# Rail_Station.net
KiCad netlist of a schematic drawn in Altium Designer
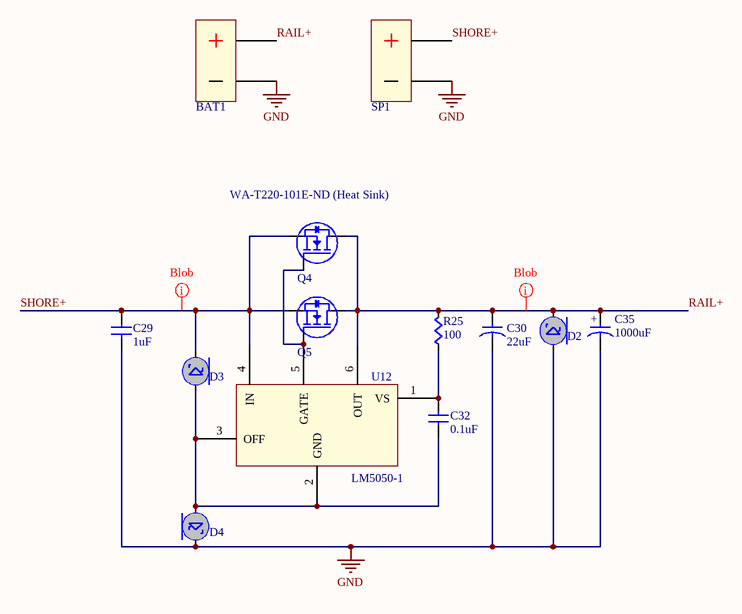
[diagram p0: Rail Station.SchDoc]

(export (version "E")
  (design (tool "Eeschema 10.0.6"))
  (components
    (comp (ref "BAT1")
      (value "BATWIRE")
      (footprint "BATWIRE12")
      (description "Two large gauge leads soldered directly to the board.")
      (libsource (lib "SubjuGator8") (part "BATWIRE"))
    )
    (comp (ref "C29")
      (value "1uF")
      (footprint "CAPC0603")
      (fields (field (name "Comment") "Cap"))
      (libsource (lib "SubjuGator8") (part "Cap"))
    )
    (comp (ref "C30")
      (value "22uF")
      (footprint "CAP22uF100V")
      (fields (field (name "Comment") "CapPol"))
      (libsource (lib "") (part "CapPol_1"))
    )
    (comp (ref "C32")
      (value "0.1uF")
      (footprint "CAPC0603")
      (fields (field (name "Comment") "Cap"))
      (libsource (lib "SubjuGator8") (part "Cap"))
    )
    (comp (ref "C35")
      (value "1000uF")
      (footprint "CAP1000uF")
      (fields (field (name "Comment") "CapPol"))
      (libsource (lib "SubjuGator8") (part "CapPol"))
    )
    (comp (ref "D2")
      (value "SMBJ60A-13-F")
      (footprint "SMBJ60A-13-F")
      (description "TVS UNIDIRECT 600W 60V SMB")
      (libsource (lib "SubjuGator8") (part "SMBJ60A-13-F"))
    )
    (comp (ref "D3")
      (value "SS16T3G")
      (footprint "SS16T3G")
      (description "DIODE SCHOTTKY 60V 1A SMA")
      (libsource (lib "") (part "SS16T3G_1"))
    )
    (comp (ref "D4")
      (value "SS16T3G")
      (footprint "SS16T3G")
      (description "DIODE SCHOTTKY 60V 1A SMA")
      (libsource (lib "SubjuGator8") (part "SS16T3G"))
    )
    (comp (ref "Q4")
      (value "IRFB3306PbF")
      (footprint "TO-220AB Heatsink Vertical")
      (description "HEXFET Power MOSFET")
      (libsource (lib "SubjuGator8") (part "IRFx3306PbF"))
    )
    (comp (ref "Q5")
      (value "IRFB3306PbF")
      (footprint "TO-220AB Heatsink Vertical")
      (description "HEXFET Power MOSFET")
      (libsource (lib "SubjuGator8") (part "IRFx3306PbF"))
    )
    (comp (ref "R25")
      (value "100")
      (footprint "RES0603")
      (fields (field (name "Comment") "Res"))
      (libsource (lib "SubjuGator8") (part "Res"))
    )
    (comp (ref "SP1")
      (value "BATWIRE")
      (footprint "BATWIRE12")
      (description "Two large gauge leads soldered directly to the board.")
      (libsource (lib "SubjuGator8") (part "BATWIRE"))
    )
    (comp (ref "U12")
      (value "LM5050-1")
      (footprint "LM5050")
      (description "High-Side OR-ing FET Controller")
      (libsource (lib "SubjuGator8") (part "LM5050"))
    )
  )
  (nets
    (net (code "1") (name "/RAIL+") (class "Default")
      (node (ref "BAT1") (pin "+") (pinfunction "+_+") (pintype "power_in"))
      (node (ref "C30") (pin "1") (pinfunction "A_1") (pintype "passive"))
      (node (ref "C35") (pin "1") (pinfunction "A_1") (pintype "passive"))
      (node (ref "D2") (pin "C") (pinfunction "C_C") (pintype "passive"))
      (node (ref "Q4") (pin "D") (pinfunction "D_D") (pintype "passive"))
      (node (ref "Q5") (pin "D") (pinfunction "D_D") (pintype "passive"))
      (node (ref "R25") (pin "1") (pinfunction "A_1") (pintype "passive"))
      (node (ref "U12") (pin "6") (pinfunction "OUT_6") (pintype "passive"))
    )
    (net (code "2") (name "/SHORE+") (class "Default")
      (node (ref "C29") (pin "1") (pinfunction "A_1") (pintype "passive"))
      (node (ref "D3") (pin "C") (pinfunction "C_C") (pintype "passive"))
      (node (ref "Q4") (pin "S") (pinfunction "S_S") (pintype "passive"))
      (node (ref "Q5") (pin "S") (pinfunction "S_S") (pintype "passive"))
      (node (ref "SP1") (pin "+") (pinfunction "+_+") (pintype "power_in"))
      (node (ref "U12") (pin "4") (pinfunction "IN_4") (pintype "passive"))
    )
    (net (code "3") (name "GND") (class "Default")
      (node (ref "BAT1") (pin "-") (pinfunction "-_-") (pintype "power_in"))
      (node (ref "C29") (pin "2") (pinfunction "B_2") (pintype "passive"))
      (node (ref "C30") (pin "2") (pinfunction "B_2") (pintype "passive"))
      (node (ref "C35") (pin "2") (pinfunction "B_2") (pintype "passive"))
      (node (ref "D2") (pin "A") (pinfunction "A_A") (pintype "passive"))
      (node (ref "D4") (pin "C") (pinfunction "C_C") (pintype "passive"))
      (node (ref "SP1") (pin "-") (pinfunction "-_-") (pintype "power_in"))
    )
    (net (code "4") (name "Net-(C32-A)") (class "Default")
      (node (ref "C32") (pin "1") (pinfunction "A_1") (pintype "passive"))
      (node (ref "R25") (pin "2") (pinfunction "B_2") (pintype "passive"))
      (node (ref "U12") (pin "1") (pinfunction "VS_1") (pintype "passive"))
    )
    (net (code "5") (name "Net-(C32-B)") (class "Default")
      (node (ref "C32") (pin "2") (pinfunction "B_2") (pintype "passive"))
      (node (ref "D3") (pin "A") (pinfunction "A_A") (pintype "passive"))
      (node (ref "D4") (pin "A") (pinfunction "A_A") (pintype "passive"))
      (node (ref "U12") (pin "2") (pinfunction "GND_2") (pintype "passive"))
      (node (ref "U12") (pin "3") (pinfunction "OFF_3") (pintype "passive"))
    )
    (net (code "6") (name "Net-(U12-GATE)") (class "Default")
      (node (ref "Q4") (pin "G") (pinfunction "G_G") (pintype "passive"))
      (node (ref "Q5") (pin "G") (pinfunction "G_G") (pintype "passive"))
      (node (ref "U12") (pin "5") (pinfunction "GATE_5") (pintype "passive"))
    )
  )
)
